# BEESP_CODE_esp32.net
KiCad netlist of a schematic drawn in Altium Designer
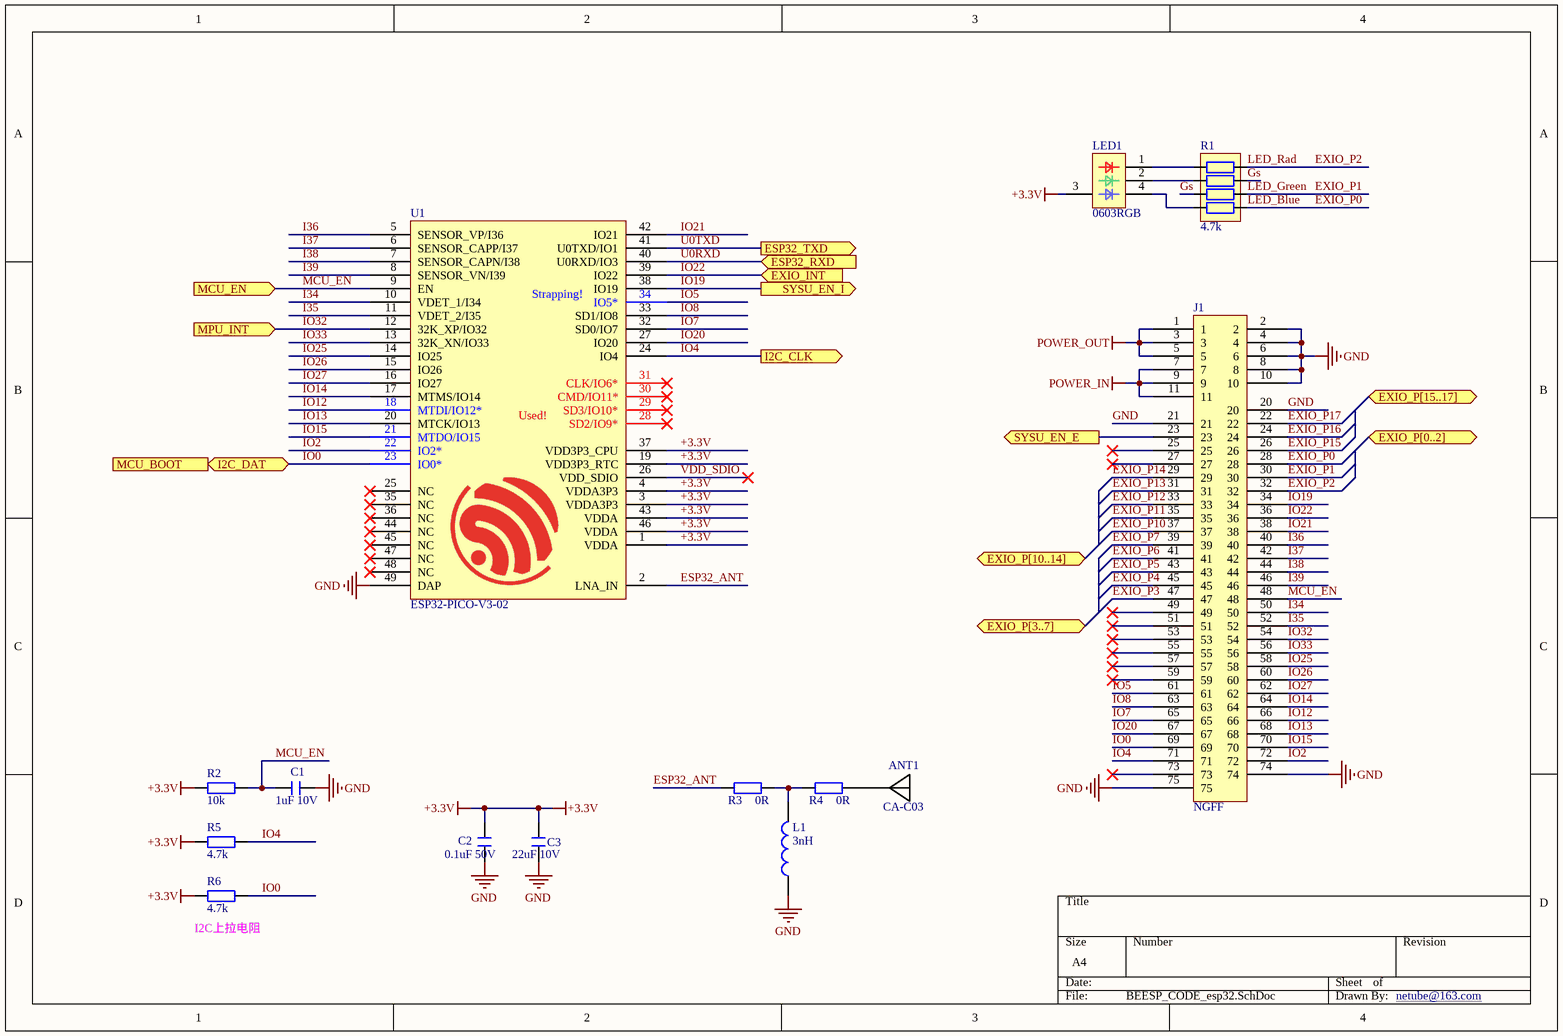
[diagram p0: BEESP_CODE_esp32.SchDoc]

(export (version "E")
  (design (tool "Eeschema 10.0.6"))
  (components
    (comp (ref "ANT1")
      (value "CA-C03")
      (footprint "CA-C03")
      (description "PCB板载天线")
      (fields (field (name "版权归属") "封装库来自淘宝 ID：黄晶宝石"))
      (libsource (lib "1.8 - WiFi天线-SMA射频座") (part "ANT1"))
    )
    (comp (ref "C1")
      (value "1uF 10V")
      (footprint "C 0402_L")
      (description "贴片电容")
      (libsource (lib "0.1 - 电阻-电容-电感") (part "C"))
    )
    (comp (ref "C2")
      (value "0.1uF 50V")
      (footprint "C 0402_L")
      (description "贴片电容")
      (libsource (lib "0.1 - 电阻-电容-电感") (part "C"))
    )
    (comp (ref "C3")
      (value "22uF 10V")
      (footprint "C 0603_L")
      (description "贴片电容")
      (libsource (lib "0.1 - 电阻-电容-电感") (part "C"))
    )
    (comp (ref "J1")
      (value "NGFF")
      (footprint "NGFF_BKey_5+6_PCB")
      (libsource (lib "PC常用接口") (part "NGFF_BKey_5+6_PCB"))
    )
    (comp (ref "L1")
      (value "3nH")
      (footprint "R 0402_L")
      (description "小功率贴片电感")
      (libsource (lib "0.1 - 电阻-电容-电感") (part "L"))
    )
    (comp (ref "LED1")
      (value "0603RGB")
      (footprint "0603RGB")
      (libsource (lib "0.3 - LED发光二极管") (part "0603RGB"))
    )
    (comp (ref "R1")
      (value "4.7k")
      (footprint "RCA-8P4R-0402")
      (description "贴片排阻")
      (libsource (lib "0.1 - 电阻-电容-电感") (part "R-8P4R"))
    )
    (comp (ref "R2")
      (value "10k")
      (footprint "R 0402_L")
      (description "贴片电阻")
      (libsource (lib "0.1 - 电阻-电容-电感") (part "R"))
    )
    (comp (ref "R3")
      (value "0R")
      (footprint "R 0402_L")
      (description "贴片电阻")
      (libsource (lib "0.1 - 电阻-电容-电感") (part "R"))
    )
    (comp (ref "R4")
      (value "0R")
      (footprint "R 0402_L")
      (description "贴片电阻")
      (libsource (lib "0.1 - 电阻-电容-电感") (part "R"))
    )
    (comp (ref "R5")
      (value "4.7k")
      (footprint "R 0402_L")
      (description "贴片电阻")
      (libsource (lib "0.1 - 电阻-电容-电感") (part "R"))
    )
    (comp (ref "R6")
      (value "4.7k")
      (footprint "R 0402_L")
      (description "贴片电阻")
      (libsource (lib "0.1 - 电阻-电容-电感") (part "R"))
    )
    (comp (ref "U1")
      (value "ESP32-PICO-V3-02")
      (footprint "QFN48 7X7_N")
      (libsource (lib "esp32") (part "ESP32-PICO-V3-02"))
    )
  )
  (nets
    (net (code "1") (name "+3.3V") (class "Default")
      (node (ref "C2") (pin "2") (pinfunction "2_2") (pintype "passive"))
      (node (ref "C3") (pin "1") (pinfunction "1_1") (pintype "passive"))
      (node (ref "LED1") (pin "3") (pinfunction "VCC_3") (pintype "passive"))
      (node (ref "R2") (pin "2") (pinfunction "2_2") (pintype "passive"))
      (node (ref "R5") (pin "2") (pinfunction "2_2") (pintype "passive"))
      (node (ref "R6") (pin "2") (pinfunction "2_2") (pintype "passive"))
      (node (ref "U1") (pin "1") (pinfunction "VDDA_1") (pintype "passive"))
      (node (ref "U1") (pin "19") (pinfunction "VDD3P3_RTC_19") (pintype "passive"))
      (node (ref "U1") (pin "3") (pinfunction "VDDA3P3_3") (pintype "passive"))
      (node (ref "U1") (pin "37") (pinfunction "VDD3P3_CPU_37") (pintype "passive"))
      (node (ref "U1") (pin "4") (pinfunction "VDDA3P3_4") (pintype "passive"))
      (node (ref "U1") (pin "43") (pinfunction "VDDA_43") (pintype "passive"))
      (node (ref "U1") (pin "46") (pinfunction "VDDA_46") (pintype "passive"))
    )
    (net (code "2") (name "/ESP32_ANT") (class "Default")
      (node (ref "R3") (pin "1") (pinfunction "1_1") (pintype "passive"))
      (node (ref "U1") (pin "2") (pinfunction "LNA_IN_2") (pintype "passive"))
    )
    (net (code "3") (name "/EXIO_P0") (class "Default")
      (node (ref "J1") (pin "28") (pinfunction "28_28") (pintype "passive"))
      (node (ref "R1") (pin "5") (pinfunction "5_5") (pintype "passive"))
    )
    (net (code "4") (name "/EXIO_P1") (class "Default")
      (node (ref "J1") (pin "30") (pinfunction "30_30") (pintype "passive"))
      (node (ref "R1") (pin "6") (pinfunction "6_6") (pintype "passive"))
    )
    (net (code "5") (name "/EXIO_P2") (class "Default")
      (node (ref "J1") (pin "32") (pinfunction "32_32") (pintype "passive"))
      (node (ref "R1") (pin "8") (pinfunction "8_8") (pintype "passive"))
    )
    (net (code "6") (name "/EXIO_P3") (class "Default")
      (node (ref "J1") (pin "47") (pinfunction "47_47") (pintype "passive"))
    )
    (net (code "7") (name "/EXIO_P4") (class "Default")
      (node (ref "J1") (pin "45") (pinfunction "45_45") (pintype "passive"))
    )
    (net (code "8") (name "/EXIO_P5") (class "Default")
      (node (ref "J1") (pin "43") (pinfunction "43_43") (pintype "passive"))
    )
    (net (code "9") (name "/EXIO_P6") (class "Default")
      (node (ref "J1") (pin "41") (pinfunction "41_41") (pintype "passive"))
    )
    (net (code "10") (name "/EXIO_P7") (class "Default")
      (node (ref "J1") (pin "39") (pinfunction "39_39") (pintype "passive"))
    )
    (net (code "11") (name "/EXIO_P10") (class "Default")
      (node (ref "J1") (pin "37") (pinfunction "37_37") (pintype "passive"))
    )
    (net (code "12") (name "/EXIO_P11") (class "Default")
      (node (ref "J1") (pin "35") (pinfunction "35_35") (pintype "passive"))
    )
    (net (code "13") (name "/EXIO_P12") (class "Default")
      (node (ref "J1") (pin "33") (pinfunction "33_33") (pintype "passive"))
    )
    (net (code "14") (name "/EXIO_P13") (class "Default")
      (node (ref "J1") (pin "31") (pinfunction "31_31") (pintype "passive"))
    )
    (net (code "15") (name "/EXIO_P14") (class "Default")
      (node (ref "J1") (pin "29") (pinfunction "29_29") (pintype "passive"))
    )
    (net (code "16") (name "/EXIO_P15") (class "Default")
      (node (ref "J1") (pin "26") (pinfunction "26_26") (pintype "passive"))
    )
    (net (code "17") (name "/EXIO_P16") (class "Default")
      (node (ref "J1") (pin "24") (pinfunction "24_24") (pintype "passive"))
    )
    (net (code "18") (name "/EXIO_P17") (class "Default")
      (node (ref "J1") (pin "22") (pinfunction "22_22") (pintype "passive"))
    )
    (net (code "23") (name "/Gs") (class "Default")
      (node (ref "R1") (pin "3") (pinfunction "3_3") (pintype "passive"))
      (node (ref "R1") (pin "7") (pinfunction "7_7") (pintype "passive"))
    )
    (net (code "24") (name "/I34") (class "Default")
      (node (ref "J1") (pin "50") (pinfunction "50_50") (pintype "passive"))
      (node (ref "U1") (pin "10") (pinfunction "VDET_1/I34_10") (pintype "passive"))
    )
    (net (code "25") (name "/I35") (class "Default")
      (node (ref "J1") (pin "52") (pinfunction "52_52") (pintype "passive"))
      (node (ref "U1") (pin "11") (pinfunction "VDET_2/I35_11") (pintype "passive"))
    )
    (net (code "26") (name "/I36") (class "Default")
      (node (ref "J1") (pin "40") (pinfunction "40_40") (pintype "passive"))
      (node (ref "U1") (pin "5") (pinfunction "SENSOR_VP/I36_5") (pintype "passive"))
    )
    (net (code "27") (name "/I37") (class "Default")
      (node (ref "J1") (pin "42") (pinfunction "42_42") (pintype "passive"))
      (node (ref "U1") (pin "6") (pinfunction "SENSOR_CAPP/I37_6") (pintype "passive"))
    )
    (net (code "28") (name "/I38") (class "Default")
      (node (ref "J1") (pin "44") (pinfunction "44_44") (pintype "passive"))
      (node (ref "U1") (pin "7") (pinfunction "SENSOR_CAPN/I38_7") (pintype "passive"))
    )
    (net (code "29") (name "/I39") (class "Default")
      (node (ref "J1") (pin "46") (pinfunction "46_46") (pintype "passive"))
      (node (ref "U1") (pin "8") (pinfunction "SENSOR_VN/I39_8") (pintype "passive"))
    )
    (net (code "30") (name "/IO0") (class "Default")
      (node (ref "J1") (pin "69") (pinfunction "69_69") (pintype "passive"))
      (node (ref "R6") (pin "1") (pinfunction "1_1") (pintype "passive"))
      (node (ref "U1") (pin "23") (pinfunction "IO0*_23") (pintype "passive"))
    )
    (net (code "31") (name "/IO2") (class "Default")
      (node (ref "J1") (pin "72") (pinfunction "72_72") (pintype "passive"))
      (node (ref "U1") (pin "22") (pinfunction "IO2*_22") (pintype "passive"))
    )
    (net (code "32") (name "/IO4") (class "Default")
      (node (ref "J1") (pin "71") (pinfunction "71_71") (pintype "passive"))
      (node (ref "R5") (pin "1") (pinfunction "1_1") (pintype "passive"))
      (node (ref "U1") (pin "24") (pinfunction "IO4_24") (pintype "passive"))
    )
    (net (code "33") (name "/IO5") (class "Default")
      (node (ref "J1") (pin "61") (pinfunction "61_61") (pintype "passive"))
      (node (ref "U1") (pin "34") (pinfunction "IO5*_34") (pintype "passive"))
    )
    (net (code "34") (name "/IO7") (class "Default")
      (node (ref "J1") (pin "65") (pinfunction "65_65") (pintype "passive"))
      (node (ref "U1") (pin "32") (pinfunction "SD0/IO7_32") (pintype "passive"))
    )
    (net (code "35") (name "/IO8") (class "Default")
      (node (ref "J1") (pin "63") (pinfunction "63_63") (pintype "passive"))
      (node (ref "U1") (pin "33") (pinfunction "SD1/IO8_33") (pintype "passive"))
    )
    (net (code "36") (name "/IO12") (class "Default")
      (node (ref "J1") (pin "66") (pinfunction "66_66") (pintype "passive"))
      (node (ref "U1") (pin "18") (pinfunction "MTDI/IO12*_18") (pintype "passive"))
    )
    (net (code "37") (name "/IO13") (class "Default")
      (node (ref "J1") (pin "68") (pinfunction "68_68") (pintype "passive"))
      (node (ref "U1") (pin "20") (pinfunction "MTCK/IO13_20") (pintype "passive"))
    )
    (net (code "38") (name "/IO14") (class "Default")
      (node (ref "J1") (pin "64") (pinfunction "64_64") (pintype "passive"))
      (node (ref "U1") (pin "17") (pinfunction "MTMS/IO14_17") (pintype "passive"))
    )
    (net (code "39") (name "/IO15") (class "Default")
      (node (ref "J1") (pin "70") (pinfunction "70_70") (pintype "passive"))
      (node (ref "U1") (pin "21") (pinfunction "MTDO/IO15_21") (pintype "passive"))
    )
    (net (code "40") (name "/IO19") (class "Default")
      (node (ref "J1") (pin "34") (pinfunction "34_34") (pintype "passive"))
      (node (ref "U1") (pin "38") (pinfunction "IO19_38") (pintype "passive"))
    )
    (net (code "41") (name "/IO20") (class "Default")
      (node (ref "J1") (pin "67") (pinfunction "67_67") (pintype "passive"))
      (node (ref "U1") (pin "27") (pinfunction "IO20_27") (pintype "passive"))
    )
    (net (code "42") (name "/IO21") (class "Default")
      (node (ref "J1") (pin "38") (pinfunction "38_38") (pintype "passive"))
      (node (ref "U1") (pin "42") (pinfunction "IO21_42") (pintype "passive"))
    )
    (net (code "43") (name "/IO22") (class "Default")
      (node (ref "J1") (pin "36") (pinfunction "36_36") (pintype "passive"))
      (node (ref "U1") (pin "39") (pinfunction "IO22_39") (pintype "passive"))
    )
    (net (code "44") (name "/IO25") (class "Default")
      (node (ref "J1") (pin "58") (pinfunction "58_58") (pintype "passive"))
      (node (ref "U1") (pin "14") (pinfunction "IO25_14") (pintype "passive"))
    )
    (net (code "45") (name "/IO26") (class "Default")
      (node (ref "J1") (pin "60") (pinfunction "60_60") (pintype "passive"))
      (node (ref "U1") (pin "15") (pinfunction "IO26_15") (pintype "passive"))
    )
    (net (code "46") (name "/IO27") (class "Default")
      (node (ref "J1") (pin "62") (pinfunction "62_62") (pintype "passive"))
      (node (ref "U1") (pin "16") (pinfunction "IO27_16") (pintype "passive"))
    )
    (net (code "47") (name "/IO32") (class "Default")
      (node (ref "J1") (pin "54") (pinfunction "54_54") (pintype "passive"))
      (node (ref "U1") (pin "12") (pinfunction "32K_XP/IO32_12") (pintype "passive"))
    )
    (net (code "48") (name "/IO33") (class "Default")
      (node (ref "J1") (pin "56") (pinfunction "56_56") (pintype "passive"))
      (node (ref "U1") (pin "13") (pinfunction "32K_XN/IO33_13") (pintype "passive"))
    )
    (net (code "50") (name "/MCU_EN") (class "Default")
      (node (ref "C1") (pin "2") (pinfunction "2_2") (pintype "passive"))
      (node (ref "J1") (pin "48") (pinfunction "48_48") (pintype "passive"))
      (node (ref "R2") (pin "1") (pinfunction "1_1") (pintype "passive"))
      (node (ref "U1") (pin "9") (pinfunction "EN_9") (pintype "passive"))
    )
    (net (code "51") (name "/SYSU_EN_E") (class "Default")
      (node (ref "J1") (pin "23") (pinfunction "23_23") (pintype "passive"))
    )
    (net (code "52") (name "/U0RXD") (class "Default")
      (node (ref "U1") (pin "40") (pinfunction "U0RXD/IO3_40") (pintype "passive"))
    )
    (net (code "53") (name "/U0TXD") (class "Default")
      (node (ref "U1") (pin "41") (pinfunction "U0TXD/IO1_41") (pintype "passive"))
    )
    (net (code "54") (name "/VDD_SDIO") (class "Default")
      (node (ref "U1") (pin "26") (pinfunction "VDD_SDIO_26") (pintype "passive+no_connect"))
    )
    (net (code "55") (name "GND") (class "Default")
      (node (ref "C1") (pin "1") (pinfunction "1_1") (pintype "passive"))
      (node (ref "C2") (pin "1") (pinfunction "1_1") (pintype "passive"))
      (node (ref "C3") (pin "2") (pinfunction "2_2") (pintype "passive"))
      (node (ref "J1") (pin "10") (pinfunction "10_10") (pintype "passive"))
      (node (ref "J1") (pin "2") (pinfunction "2_2") (pintype "passive"))
      (node (ref "J1") (pin "20") (pinfunction "20_20") (pintype "passive"))
      (node (ref "J1") (pin "21") (pinfunction "21_21") (pintype "passive"))
      (node (ref "J1") (pin "4") (pinfunction "4_4") (pintype "passive"))
      (node (ref "J1") (pin "6") (pinfunction "6_6") (pintype "passive"))
      (node (ref "J1") (pin "74") (pinfunction "74_74") (pintype "passive"))
      (node (ref "J1") (pin "75") (pinfunction "75_75") (pintype "passive"))
      (node (ref "J1") (pin "8") (pinfunction "8_8") (pintype "passive"))
      (node (ref "L1") (pin "1") (pinfunction "1_1") (pintype "passive"))
      (node (ref "U1") (pin "49") (pinfunction "DAP_49") (pintype "passive"))
    )
    (net (code "56") (name "Net-(ANT1-Pad1)") (class "Default")
      (node (ref "ANT1") (pin "1") (pinfunction "1_1") (pintype "passive"))
      (node (ref "R4") (pin "2") (pinfunction "2_2") (pintype "passive"))
    )
    (net (code "57") (name "Net-(L1-Pad2)") (class "Default")
      (node (ref "L1") (pin "2") (pinfunction "2_2") (pintype "passive"))
      (node (ref "R3") (pin "2") (pinfunction "2_2") (pintype "passive"))
      (node (ref "R4") (pin "1") (pinfunction "1_1") (pintype "passive"))
    )
    (net (code "58") (name "Net-(LED1-B)") (class "Default")
      (node (ref "LED1") (pin "4") (pinfunction "B_4") (pintype "passive"))
      (node (ref "R1") (pin "4") (pinfunction "4_4") (pintype "passive"))
    )
    (net (code "59") (name "Net-(LED1-G)") (class "Default")
      (node (ref "LED1") (pin "2") (pinfunction "G_2") (pintype "passive"))
      (node (ref "R1") (pin "2") (pinfunction "2_2") (pintype "passive"))
    )
    (net (code "60") (name "Net-(LED1-R)") (class "Default")
      (node (ref "LED1") (pin "1") (pinfunction "R_1") (pintype "passive"))
      (node (ref "R1") (pin "1") (pinfunction "1_1") (pintype "passive"))
    )
    (net (code "61") (name "POWER_IN") (class "Default")
      (node (ref "J1") (pin "11") (pinfunction "11_11") (pintype "passive"))
      (node (ref "J1") (pin "7") (pinfunction "7_7") (pintype "passive"))
      (node (ref "J1") (pin "9") (pinfunction "9_9") (pintype "passive"))
    )
    (net (code "62") (name "POWER_OUT") (class "Default")
      (node (ref "J1") (pin "1") (pinfunction "1_1") (pintype "passive"))
      (node (ref "J1") (pin "3") (pinfunction "3_3") (pintype "passive"))
      (node (ref "J1") (pin "5") (pinfunction "5_5") (pintype "passive"))
    )
    (net (code "63") (name "unconnected-(J1-Pad25)") (class "Default")
      (node (ref "J1") (pin "25") (pinfunction "25_25") (pintype "passive+no_connect"))
    )
    (net (code "64") (name "unconnected-(J1-Pad27)") (class "Default")
      (node (ref "J1") (pin "27") (pinfunction "27_27") (pintype "passive+no_connect"))
    )
    (net (code "65") (name "unconnected-(J1-Pad49)") (class "Default")
      (node (ref "J1") (pin "49") (pinfunction "49_49") (pintype "passive+no_connect"))
    )
    (net (code "66") (name "unconnected-(J1-Pad51)") (class "Default")
      (node (ref "J1") (pin "51") (pinfunction "51_51") (pintype "passive+no_connect"))
    )
    (net (code "67") (name "unconnected-(J1-Pad53)") (class "Default")
      (node (ref "J1") (pin "53") (pinfunction "53_53") (pintype "passive+no_connect"))
    )
    (net (code "68") (name "unconnected-(J1-Pad55)") (class "Default")
      (node (ref "J1") (pin "55") (pinfunction "55_55") (pintype "passive+no_connect"))
    )
    (net (code "69") (name "unconnected-(J1-Pad57)") (class "Default")
      (node (ref "J1") (pin "57") (pinfunction "57_57") (pintype "passive+no_connect"))
    )
    (net (code "70") (name "unconnected-(J1-Pad59)") (class "Default")
      (node (ref "J1") (pin "59") (pinfunction "59_59") (pintype "passive+no_connect"))
    )
    (net (code "71") (name "unconnected-(J1-Pad73)") (class "Default")
      (node (ref "J1") (pin "73") (pinfunction "73_73") (pintype "passive+no_connect"))
    )
    (net (code "72") (name "unconnected-(U1-CLK{slash}IO6*-Pad31)") (class "Default")
      (node (ref "U1") (pin "31") (pinfunction "CLK/IO6*_31") (pintype "passive+no_connect"))
    )
    (net (code "73") (name "unconnected-(U1-CMD{slash}IO11*-Pad30)") (class "Default")
      (node (ref "U1") (pin "30") (pinfunction "CMD/IO11*_30") (pintype "passive+no_connect"))
    )
    (net (code "74") (name "unconnected-(U1-NC-Pad25)") (class "Default")
      (node (ref "U1") (pin "25") (pinfunction "NC_25") (pintype "passive+no_connect"))
    )
    (net (code "75") (name "unconnected-(U1-NC-Pad35)") (class "Default")
      (node (ref "U1") (pin "35") (pinfunction "NC_35") (pintype "passive+no_connect"))
    )
    (net (code "76") (name "unconnected-(U1-NC-Pad36)") (class "Default")
      (node (ref "U1") (pin "36") (pinfunction "NC_36") (pintype "passive+no_connect"))
    )
    (net (code "77") (name "unconnected-(U1-NC-Pad44)") (class "Default")
      (node (ref "U1") (pin "44") (pinfunction "NC_44") (pintype "passive+no_connect"))
    )
    (net (code "78") (name "unconnected-(U1-NC-Pad45)") (class "Default")
      (node (ref "U1") (pin "45") (pinfunction "NC_45") (pintype "passive+no_connect"))
    )
    (net (code "79") (name "unconnected-(U1-NC-Pad47)") (class "Default")
      (node (ref "U1") (pin "47") (pinfunction "NC_47") (pintype "passive+no_connect"))
    )
    (net (code "80") (name "unconnected-(U1-NC-Pad48)") (class "Default")
      (node (ref "U1") (pin "48") (pinfunction "NC_48") (pintype "passive+no_connect"))
    )
    (net (code "81") (name "unconnected-(U1-SD2{slash}IO9*-Pad28)") (class "Default")
      (node (ref "U1") (pin "28") (pinfunction "SD2/IO9*_28") (pintype "passive+no_connect"))
    )
    (net (code "82") (name "unconnected-(U1-SD3{slash}IO10*-Pad29)") (class "Default")
      (node (ref "U1") (pin "29") (pinfunction "SD3/IO10*_29") (pintype "passive+no_connect"))
    )
  )
)
